# prototype_dual_channel.net
KiCad netlist of a schematic drawn in Altium Designer
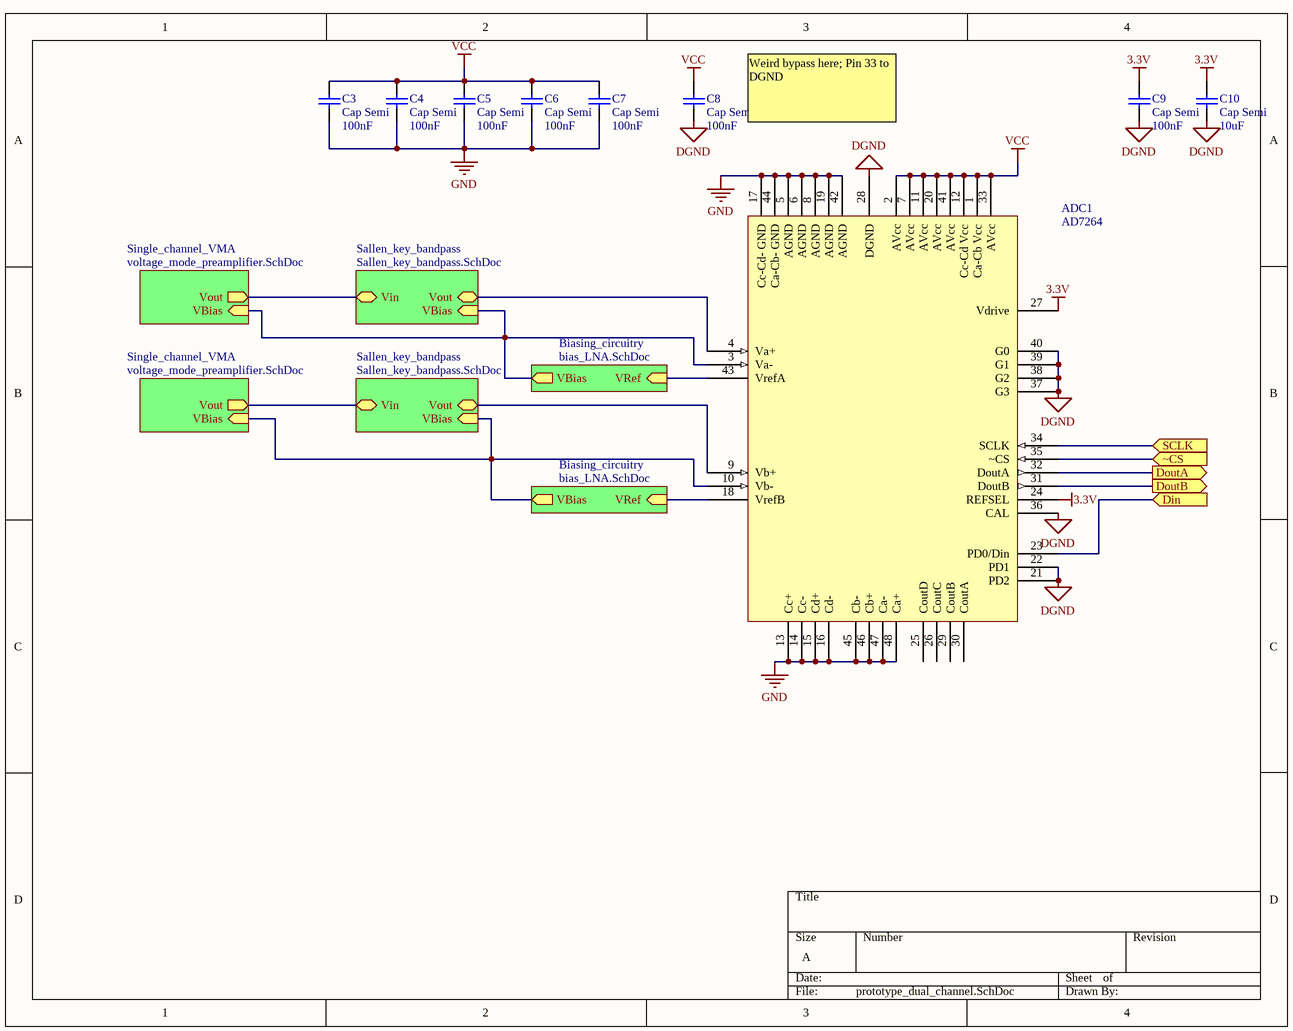
[diagram p0: prototype_dual_channel.SchDoc]

(export (version "E")
  (design (tool "Eeschema 10.0.6"))
  (components
    (comp (ref "ADC1")
      (value "AD7264")
      (footprint "TSQFP50P900X900-48N")
      (description "AD7264 - 14 bit 1MSPS 2 channel ADC")
      (libsource (lib "Sonar_board") (part "AD7264"))
    )
    (comp (ref "C3")
      (value "Cap Semi")
      (footprint "C0805")
      (description "Capacitor (Semiconductor SIM Model)")
      (fields (field (name "ALTIUM_VALUE") "100nF") (field (name "PUBLISHER") "Altium Limited"))
      (libsource (lib "Miscellaneous Devices") (part "Cap Semi"))
    )
    (comp (ref "C4")
      (value "Cap Semi")
      (footprint "C0805")
      (description "Capacitor (Semiconductor SIM Model)")
      (fields (field (name "ALTIUM_VALUE") "100nF") (field (name "PUBLISHER") "Altium Limited"))
      (libsource (lib "Miscellaneous Devices") (part "Cap Semi"))
    )
    (comp (ref "C5")
      (value "Cap Semi")
      (footprint "C0805")
      (description "Capacitor (Semiconductor SIM Model)")
      (fields (field (name "ALTIUM_VALUE") "100nF") (field (name "PUBLISHER") "Altium Limited"))
      (libsource (lib "Miscellaneous Devices") (part "Cap Semi"))
    )
    (comp (ref "C6")
      (value "Cap Semi")
      (footprint "C0805")
      (description "Capacitor (Semiconductor SIM Model)")
      (fields (field (name "ALTIUM_VALUE") "100nF") (field (name "PUBLISHER") "Altium Limited"))
      (libsource (lib "Miscellaneous Devices") (part "Cap Semi"))
    )
    (comp (ref "C7")
      (value "Cap Semi")
      (footprint "C0805")
      (description "Capacitor (Semiconductor SIM Model)")
      (fields (field (name "ALTIUM_VALUE") "100nF") (field (name "PUBLISHER") "Altium Limited"))
      (libsource (lib "Miscellaneous Devices") (part "Cap Semi"))
    )
    (comp (ref "C8")
      (value "Cap Semi")
      (footprint "C0805")
      (description "Capacitor (Semiconductor SIM Model)")
      (fields (field (name "ALTIUM_VALUE") "100nF") (field (name "PUBLISHER") "Altium Limited"))
      (libsource (lib "Miscellaneous Devices") (part "Cap Semi"))
    )
    (comp (ref "C9")
      (value "Cap Semi")
      (footprint "C0805")
      (description "Capacitor (Semiconductor SIM Model)")
      (fields (field (name "ALTIUM_VALUE") "100nF") (field (name "PUBLISHER") "Altium Limited"))
      (libsource (lib "Miscellaneous Devices") (part "Cap Semi"))
    )
    (comp (ref "C10")
      (value "Cap Semi")
      (footprint "C0805")
      (description "Capacitor (Semiconductor SIM Model)")
      (fields (field (name "ALTIUM_VALUE") "10uF") (field (name "PUBLISHER") "Altium Limited"))
      (libsource (lib "Miscellaneous Devices") (part "Cap Semi"))
    )
  )
  (nets
    (net (code "1") (name "/Din") (class "Default")
      (node (ref "ADC1") (pin "23") (pinfunction "PD0/Din_23") (pintype "passive"))
    )
    (net (code "2") (name "/DoutA") (class "Default")
      (node (ref "ADC1") (pin "32") (pinfunction "DoutA_32") (pintype "output"))
    )
    (net (code "3") (name "/DoutB") (class "Default")
      (node (ref "ADC1") (pin "31") (pinfunction "DoutB_31") (pintype "output"))
    )
    (net (code "4") (name "/SCLK") (class "Default")
      (node (ref "ADC1") (pin "34") (pinfunction "SCLK_34") (pintype "input"))
    )
    (net (code "5") (name "/VBias") (class "Default")
      (node (ref "ADC1") (pin "10") (pinfunction "Vb-_10") (pintype "input"))
    )
    (net (code "6") (name "/VBias_1") (class "Default")
      (node (ref "ADC1") (pin "3") (pinfunction "Va-_3") (pintype "input"))
    )
    (net (code "7") (name "/VRef") (class "Default")
      (node (ref "ADC1") (pin "43") (pinfunction "VrefA_43") (pintype "passive"))
    )
    (net (code "8") (name "/VRef_1") (class "Default")
      (node (ref "ADC1") (pin "18") (pinfunction "VrefB_18") (pintype "passive"))
    )
    (net (code "10") (name "/Vout_1") (class "Default")
      (node (ref "ADC1") (pin "4") (pinfunction "Va+_4") (pintype "input"))
    )
    (net (code "11") (name "/Vout_2") (class "Default")
      (node (ref "ADC1") (pin "9") (pinfunction "Vb+_9") (pintype "input"))
    )
    (net (code "13") (name "/~CS") (class "Default")
      (node (ref "ADC1") (pin "35") (pinfunction "~CS_35") (pintype "input"))
    )
    (net (code "14") (name "3.3V") (class "Default")
      (node (ref "ADC1") (pin "24") (pinfunction "REFSEL_24") (pintype "passive"))
      (node (ref "ADC1") (pin "27") (pinfunction "Vdrive_27") (pintype "passive"))
      (node (ref "C10") (pin "2") (pinfunction "2_2") (pintype "passive"))
      (node (ref "C9") (pin "2") (pinfunction "2_2") (pintype "passive"))
    )
    (net (code "15") (name "DGND") (class "Default")
      (node (ref "ADC1") (pin "21") (pinfunction "PD2_21") (pintype "passive"))
      (node (ref "ADC1") (pin "22") (pinfunction "PD1_22") (pintype "passive"))
      (node (ref "ADC1") (pin "28") (pinfunction "DGND_28") (pintype "passive"))
      (node (ref "ADC1") (pin "36") (pinfunction "CAL_36") (pintype "passive"))
      (node (ref "ADC1") (pin "37") (pinfunction "G3_37") (pintype "passive"))
      (node (ref "ADC1") (pin "38") (pinfunction "G2_38") (pintype "passive"))
      (node (ref "ADC1") (pin "39") (pinfunction "G1_39") (pintype "passive"))
      (node (ref "ADC1") (pin "40") (pinfunction "G0_40") (pintype "passive"))
      (node (ref "C10") (pin "1") (pinfunction "1_1") (pintype "passive"))
      (node (ref "C8") (pin "1") (pinfunction "1_1") (pintype "passive"))
      (node (ref "C9") (pin "1") (pinfunction "1_1") (pintype "passive"))
    )
    (net (code "16") (name "GND") (class "Default")
      (node (ref "ADC1") (pin "13") (pinfunction "Cc+_13") (pintype "passive"))
      (node (ref "ADC1") (pin "14") (pinfunction "Cc-_14") (pintype "passive"))
      (node (ref "ADC1") (pin "15") (pinfunction "Cd+_15") (pintype "passive"))
      (node (ref "ADC1") (pin "16") (pinfunction "Cd-_16") (pintype "passive"))
      (node (ref "ADC1") (pin "17") (pinfunction "Cc-Cd-_GND_17") (pintype "passive"))
      (node (ref "ADC1") (pin "19") (pinfunction "AGND_19") (pintype "passive"))
      (node (ref "ADC1") (pin "42") (pinfunction "AGND_42") (pintype "passive"))
      (node (ref "ADC1") (pin "44") (pinfunction "Ca-Cb-_GND_44") (pintype "passive"))
      (node (ref "ADC1") (pin "45") (pinfunction "Cb-_45") (pintype "passive"))
      (node (ref "ADC1") (pin "46") (pinfunction "Cb+_46") (pintype "passive"))
      (node (ref "ADC1") (pin "47") (pinfunction "Ca-_47") (pintype "passive"))
      (node (ref "ADC1") (pin "48") (pinfunction "Ca+_48") (pintype "passive"))
      (node (ref "ADC1") (pin "5") (pinfunction "AGND_5") (pintype "passive"))
      (node (ref "ADC1") (pin "6") (pinfunction "AGND_6") (pintype "passive"))
      (node (ref "ADC1") (pin "8") (pinfunction "AGND_8") (pintype "passive"))
      (node (ref "C3") (pin "1") (pinfunction "1_1") (pintype "passive"))
      (node (ref "C4") (pin "1") (pinfunction "1_1") (pintype "passive"))
      (node (ref "C5") (pin "1") (pinfunction "1_1") (pintype "passive"))
      (node (ref "C6") (pin "1") (pinfunction "1_1") (pintype "passive"))
      (node (ref "C7") (pin "1") (pinfunction "1_1") (pintype "passive"))
    )
    (net (code "17") (name "VCC") (class "Default")
      (node (ref "ADC1") (pin "1") (pinfunction "Ca-Cb_Vcc_1") (pintype "passive"))
      (node (ref "ADC1") (pin "11") (pinfunction "AVcc_11") (pintype "passive"))
      (node (ref "ADC1") (pin "12") (pinfunction "Cc-Cd_Vcc_12") (pintype "passive"))
      (node (ref "ADC1") (pin "2") (pinfunction "AVcc_2") (pintype "passive"))
      (node (ref "ADC1") (pin "20") (pinfunction "AVcc_20") (pintype "passive"))
      (node (ref "ADC1") (pin "33") (pinfunction "AVcc_33") (pintype "passive"))
      (node (ref "ADC1") (pin "41") (pinfunction "AVcc_41") (pintype "passive"))
      (node (ref "ADC1") (pin "7") (pinfunction "AVcc_7") (pintype "passive"))
      (node (ref "C3") (pin "2") (pinfunction "2_2") (pintype "passive"))
      (node (ref "C4") (pin "2") (pinfunction "2_2") (pintype "passive"))
      (node (ref "C5") (pin "2") (pinfunction "2_2") (pintype "passive"))
      (node (ref "C6") (pin "2") (pinfunction "2_2") (pintype "passive"))
      (node (ref "C7") (pin "2") (pinfunction "2_2") (pintype "passive"))
      (node (ref "C8") (pin "2") (pinfunction "2_2") (pintype "passive"))
    )
    (net (code "18") (name "unconnected-(ADC1-CoutA-Pad30)") (class "Default")
      (node (ref "ADC1") (pin "30") (pinfunction "CoutA_30") (pintype "passive"))
    )
    (net (code "19") (name "unconnected-(ADC1-CoutB-Pad29)") (class "Default")
      (node (ref "ADC1") (pin "29") (pinfunction "CoutB_29") (pintype "passive"))
    )
    (net (code "20") (name "unconnected-(ADC1-CoutC-Pad26)") (class "Default")
      (node (ref "ADC1") (pin "26") (pinfunction "CoutC_26") (pintype "passive"))
    )
    (net (code "21") (name "unconnected-(ADC1-CoutD-Pad25)") (class "Default")
      (node (ref "ADC1") (pin "25") (pinfunction "CoutD_25") (pintype "passive"))
    )
  )
)
